# 7ChannelSpectrumAnalyzer.net
KiCad netlist of a schematic drawn in EAGLE
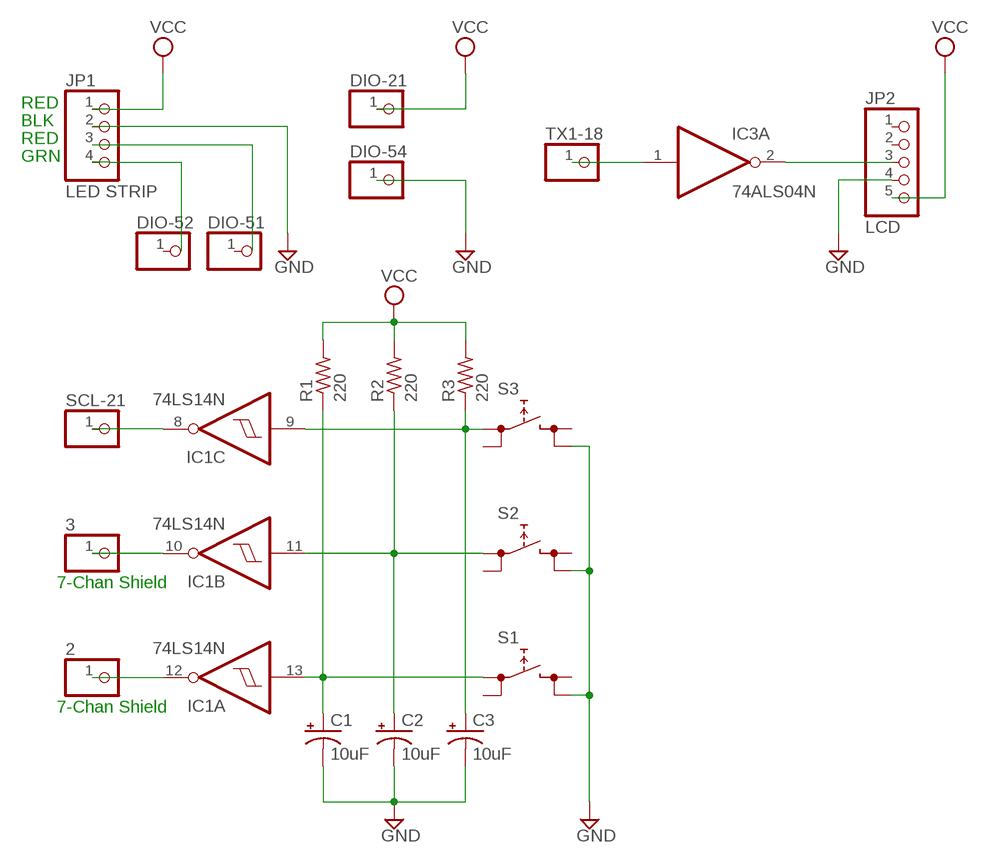
[diagram p0: schematic, sheet 1]

(export (version "E")
  (design (tool "Eeschema 10.0.6"))
  (components
    (comp (ref "2")
      (value "PINHD-1X1")
      (footprint "eagle-import:1X01")
      (libsource (lib "eagle-import") (part "PINHD-1X1"))
    )
    (comp (ref "3")
      (value "PINHD-1X1")
      (footprint "eagle-import:1X01")
      (libsource (lib "eagle-import") (part "PINHD-1X1"))
    )
    (comp (ref "C1")
      (value "10uF")
      (footprint "eagle-import:E5-8,5")
      (libsource (lib "eagle-import") (part "CPOL-USE5-8.5"))
    )
    (comp (ref "C2")
      (value "10uF")
      (footprint "eagle-import:E5-8,5")
      (libsource (lib "eagle-import") (part "CPOL-USE5-8.5"))
    )
    (comp (ref "C3")
      (value "10uF")
      (footprint "eagle-import:E5-8,5")
      (libsource (lib "eagle-import") (part "CPOL-USE5-8.5"))
    )
    (comp (ref "DIO-21")
      (value "PINHD-1X1")
      (footprint "eagle-import:1X01")
      (libsource (lib "eagle-import") (part "PINHD-1X1"))
    )
    (comp (ref "DIO-51")
      (value "PINHD-1X1")
      (footprint "eagle-import:1X01")
      (libsource (lib "eagle-import") (part "PINHD-1X1"))
    )
    (comp (ref "DIO-52")
      (value "PINHD-1X1")
      (footprint "eagle-import:1X01")
      (libsource (lib "eagle-import") (part "PINHD-1X1"))
    )
    (comp (ref "DIO-54")
      (value "PINHD-1X1")
      (footprint "eagle-import:1X01")
      (libsource (lib "eagle-import") (part "PINHD-1X1"))
    )
    (comp (ref "IC1")
      (value "74LS14N")
      (footprint "eagle-import:DIL14")
      (libsource (lib "eagle-import") (part "7414NLS"))
    )
    (comp (ref "IC3")
      (value "74ALS04N")
      (footprint "eagle-import:DIL14")
      (libsource (lib "eagle-import") (part "7404NALS"))
    )
    (comp (ref "JP1")
      (value "LED STRIP")
      (footprint "eagle-import:1X04")
      (libsource (lib "eagle-import") (part "PINHD-1X4"))
    )
    (comp (ref "JP2")
      (value "LCD")
      (footprint "eagle-import:1X05")
      (libsource (lib "eagle-import") (part "PINHD-1X5"))
    )
    (comp (ref "R1")
      (value "220")
      (footprint "eagle-import:0204_7")
      (libsource (lib "eagle-import") (part "R-US_0204/7"))
    )
    (comp (ref "R2")
      (value "220")
      (footprint "eagle-import:0204_7")
      (libsource (lib "eagle-import") (part "R-US_0204/7"))
    )
    (comp (ref "R3")
      (value "220")
      (footprint "eagle-import:0204_7")
      (libsource (lib "eagle-import") (part "R-US_0204/7"))
    )
    (comp (ref "S1")
      (value "REKN")
      (footprint "eagle-import:REKN")
      (libsource (lib "eagle-import") (part "REKN"))
    )
    (comp (ref "S2")
      (value "REKN")
      (footprint "eagle-import:REKN")
      (libsource (lib "eagle-import") (part "REKN"))
    )
    (comp (ref "S3")
      (value "REKN")
      (footprint "eagle-import:REKN")
      (libsource (lib "eagle-import") (part "REKN"))
    )
    (comp (ref "SCL-21")
      (value "PINHD-1X1")
      (footprint "eagle-import:1X01")
      (libsource (lib "eagle-import") (part "PINHD-1X1"))
    )
    (comp (ref "TX1-18")
      (value "PINHD-1X1")
      (footprint "eagle-import:1X01")
      (libsource (lib "eagle-import") (part "PINHD-1X1"))
    )
  )
  (nets
    (net (code "1") (name "GND") (class "Default")
      (node (ref "C1") (pin "-") (pinfunction "-_-") (pintype "passive"))
      (node (ref "C2") (pin "-") (pinfunction "-_-") (pintype "passive"))
      (node (ref "C3") (pin "-") (pinfunction "-_-") (pintype "passive"))
      (node (ref "DIO-54") (pin "1") (pinfunction "1_1") (pintype "passive"))
      (node (ref "JP1") (pin "2") (pinfunction "2_2") (pintype "passive"))
      (node (ref "JP2") (pin "4") (pinfunction "4_4") (pintype "passive"))
      (node (ref "S1") (pin "1B") (pinfunction "1_1B") (pintype "passive"))
      (node (ref "S2") (pin "1B") (pinfunction "1_1B") (pintype "passive"))
      (node (ref "S3") (pin "1B") (pinfunction "1_1B") (pintype "passive"))
    )
    (net (code "2") (name "Net-(IC1A-I)") (class "Default")
      (node (ref "C1") (pin "+") (pinfunction "+_+") (pintype "passive"))
      (node (ref "IC1") (pin "13") (pinfunction "I_13") (pintype "input"))
      (node (ref "R1") (pin "1") (pinfunction "1_1") (pintype "passive"))
      (node (ref "S1") (pin "0A") (pinfunction "0_0A") (pintype "passive"))
    )
    (net (code "3") (name "Net-(IC1A-O)") (class "Default")
      (node (ref "2") (pin "1") (pinfunction "1_1") (pintype "passive"))
      (node (ref "IC1") (pin "12") (pinfunction "O_12") (pintype "output"))
    )
    (net (code "4") (name "Net-(IC1B-I)") (class "Default")
      (node (ref "C2") (pin "+") (pinfunction "+_+") (pintype "passive"))
      (node (ref "IC1") (pin "11") (pinfunction "I_11") (pintype "input"))
      (node (ref "R2") (pin "1") (pinfunction "1_1") (pintype "passive"))
      (node (ref "S2") (pin "0A") (pinfunction "0_0A") (pintype "passive"))
    )
    (net (code "5") (name "Net-(IC1B-O)") (class "Default")
      (node (ref "3") (pin "1") (pinfunction "1_1") (pintype "passive"))
      (node (ref "IC1") (pin "10") (pinfunction "O_10") (pintype "output"))
    )
    (net (code "6") (name "Net-(IC1C-I)") (class "Default")
      (node (ref "C3") (pin "+") (pinfunction "+_+") (pintype "passive"))
      (node (ref "IC1") (pin "9") (pinfunction "I_9") (pintype "input"))
      (node (ref "R3") (pin "1") (pinfunction "1_1") (pintype "passive"))
      (node (ref "S3") (pin "0A") (pinfunction "0_0A") (pintype "passive"))
    )
    (net (code "7") (name "Net-(IC1C-O)") (class "Default")
      (node (ref "IC1") (pin "8") (pinfunction "O_8") (pintype "output"))
      (node (ref "SCL-21") (pin "1") (pinfunction "1_1") (pintype "passive"))
    )
    (net (code "8") (name "Net-(IC3A-I)") (class "Default")
      (node (ref "IC3") (pin "1") (pinfunction "I_1") (pintype "input"))
      (node (ref "TX1-18") (pin "1") (pinfunction "1_1") (pintype "passive"))
    )
    (net (code "9") (name "Net-(IC3A-O)") (class "Default")
      (node (ref "IC3") (pin "2") (pinfunction "O_2") (pintype "output"))
      (node (ref "JP2") (pin "3") (pinfunction "3_3") (pintype "passive"))
    )
    (net (code "10") (name "VCC") (class "Default")
      (node (ref "DIO-21") (pin "1") (pinfunction "1_1") (pintype "passive"))
      (node (ref "JP1") (pin "1") (pinfunction "1_1") (pintype "passive"))
      (node (ref "JP2") (pin "5") (pinfunction "5_5") (pintype "passive"))
      (node (ref "R1") (pin "2") (pinfunction "2_2") (pintype "passive"))
      (node (ref "R2") (pin "2") (pinfunction "2_2") (pintype "passive"))
      (node (ref "R3") (pin "2") (pinfunction "2_2") (pintype "passive"))
    )
    (net (code "11") (name "unconnected-(DIO-51-Pad1)") (class "Default")
      (node (ref "DIO-51") (pin "1") (pinfunction "1_1") (pintype "passive"))
    )
    (net (code "12") (name "unconnected-(DIO-52-Pad1)") (class "Default")
      (node (ref "DIO-52") (pin "1") (pinfunction "1_1") (pintype "passive"))
    )
    (net (code "13") (name "unconnected-(JP1-Pad3)") (class "Default")
      (node (ref "JP1") (pin "3") (pinfunction "3_3") (pintype "passive"))
    )
    (net (code "14") (name "unconnected-(JP1-Pad4)") (class "Default")
      (node (ref "JP1") (pin "4") (pinfunction "4_4") (pintype "passive"))
    )
    (net (code "15") (name "unconnected-(JP2-Pad1)") (class "Default")
      (node (ref "JP2") (pin "1") (pinfunction "1_1") (pintype "passive"))
    )
    (net (code "16") (name "unconnected-(JP2-Pad2)") (class "Default")
      (node (ref "JP2") (pin "2") (pinfunction "2_2") (pintype "passive"))
    )
    (net (code "17") (name "unconnected-(S1-0-Pad0B)") (class "Default")
      (node (ref "S1") (pin "0B") (pinfunction "0_0B") (pintype "passive"))
    )
    (net (code "18") (name "unconnected-(S1-1-Pad1A)") (class "Default")
      (node (ref "S1") (pin "1A") (pinfunction "1_1A") (pintype "passive"))
    )
    (net (code "19") (name "unconnected-(S2-0-Pad0B)") (class "Default")
      (node (ref "S2") (pin "0B") (pinfunction "0_0B") (pintype "passive"))
    )
    (net (code "20") (name "unconnected-(S2-1-Pad1A)") (class "Default")
      (node (ref "S2") (pin "1A") (pinfunction "1_1A") (pintype "passive"))
    )
    (net (code "21") (name "unconnected-(S3-0-Pad0B)") (class "Default")
      (node (ref "S3") (pin "0B") (pinfunction "0_0B") (pintype "passive"))
    )
    (net (code "22") (name "unconnected-(S3-1-Pad1A)") (class "Default")
      (node (ref "S3") (pin "1A") (pinfunction "1_1A") (pintype "passive"))
    )
  )
)
